# R123A.net
KiCad netlist of a schematic drawn in EAGLE
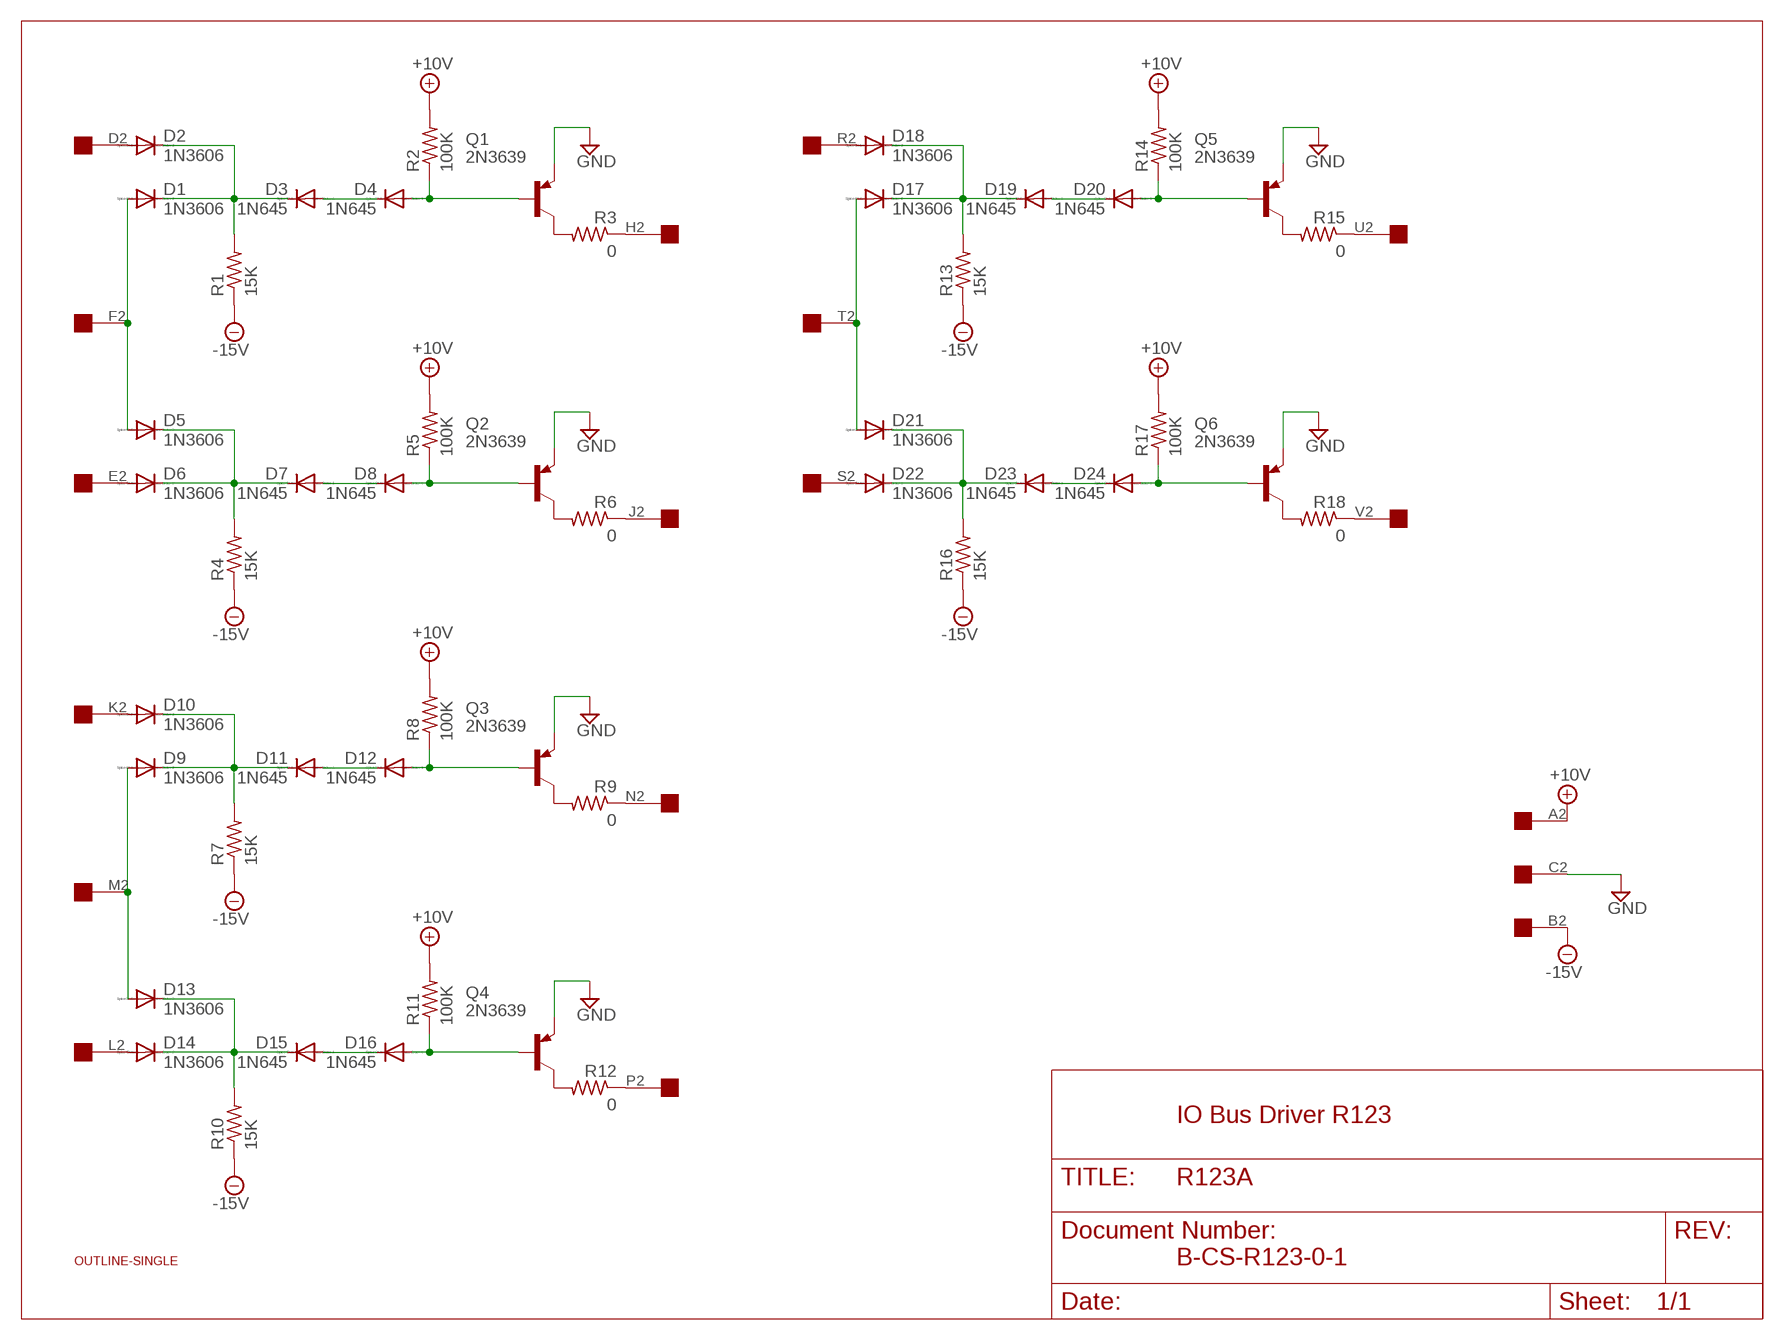
[diagram p0: schematic, sheet 1]

(export (version "E")
  (design (tool "Eeschema 10.0.6"))
  (components
    (comp (ref "D1")
      (value "1N3606")
      (footprint "eagle-import:DO35-10")
      (libsource (lib "eagle-import") (part "1N4148DO35-10"))
    )
    (comp (ref "D2")
      (value "1N3606")
      (footprint "eagle-import:DO35-10")
      (libsource (lib "eagle-import") (part "1N4148DO35-10"))
    )
    (comp (ref "D3")
      (value "1N645")
      (footprint "eagle-import:DO35-10")
      (libsource (lib "eagle-import") (part "1N4148DO35-10"))
    )
    (comp (ref "D4")
      (value "1N645")
      (footprint "eagle-import:DO35-10")
      (libsource (lib "eagle-import") (part "1N4148DO35-10"))
    )
    (comp (ref "D5")
      (value "1N3606")
      (footprint "eagle-import:DO35-10")
      (libsource (lib "eagle-import") (part "1N4148DO35-10"))
    )
    (comp (ref "D6")
      (value "1N3606")
      (footprint "eagle-import:DO35-10")
      (libsource (lib "eagle-import") (part "1N4148DO35-10"))
    )
    (comp (ref "D7")
      (value "1N645")
      (footprint "eagle-import:DO35-10")
      (libsource (lib "eagle-import") (part "1N4148DO35-10"))
    )
    (comp (ref "D8")
      (value "1N645")
      (footprint "eagle-import:DO35-10")
      (libsource (lib "eagle-import") (part "1N4148DO35-10"))
    )
    (comp (ref "D9")
      (value "1N3606")
      (footprint "eagle-import:DO35-10")
      (libsource (lib "eagle-import") (part "1N4148DO35-10"))
    )
    (comp (ref "D10")
      (value "1N3606")
      (footprint "eagle-import:DO35-10")
      (libsource (lib "eagle-import") (part "1N4148DO35-10"))
    )
    (comp (ref "D11")
      (value "1N645")
      (footprint "eagle-import:DO35-10")
      (libsource (lib "eagle-import") (part "1N4148DO35-10"))
    )
    (comp (ref "D12")
      (value "1N645")
      (footprint "eagle-import:DO35-10")
      (libsource (lib "eagle-import") (part "1N4148DO35-10"))
    )
    (comp (ref "D13")
      (value "1N3606")
      (footprint "eagle-import:DO35-10")
      (libsource (lib "eagle-import") (part "1N4148DO35-10"))
    )
    (comp (ref "D14")
      (value "1N3606")
      (footprint "eagle-import:DO35-10")
      (libsource (lib "eagle-import") (part "1N4148DO35-10"))
    )
    (comp (ref "D15")
      (value "1N645")
      (footprint "eagle-import:DO35-10")
      (libsource (lib "eagle-import") (part "1N4148DO35-10"))
    )
    (comp (ref "D16")
      (value "1N645")
      (footprint "eagle-import:DO35-10")
      (libsource (lib "eagle-import") (part "1N4148DO35-10"))
    )
    (comp (ref "D17")
      (value "1N3606")
      (footprint "eagle-import:DO35-10")
      (libsource (lib "eagle-import") (part "1N4148DO35-10"))
    )
    (comp (ref "D18")
      (value "1N3606")
      (footprint "eagle-import:DO35-10")
      (libsource (lib "eagle-import") (part "1N4148DO35-10"))
    )
    (comp (ref "D19")
      (value "1N645")
      (footprint "eagle-import:DO35-10")
      (libsource (lib "eagle-import") (part "1N4148DO35-10"))
    )
    (comp (ref "D20")
      (value "1N645")
      (footprint "eagle-import:DO35-10")
      (libsource (lib "eagle-import") (part "1N4148DO35-10"))
    )
    (comp (ref "D21")
      (value "1N3606")
      (footprint "eagle-import:DO35-10")
      (libsource (lib "eagle-import") (part "1N4148DO35-10"))
    )
    (comp (ref "D22")
      (value "1N3606")
      (footprint "eagle-import:DO35-10")
      (libsource (lib "eagle-import") (part "1N4148DO35-10"))
    )
    (comp (ref "D23")
      (value "1N645")
      (footprint "eagle-import:DO35-10")
      (libsource (lib "eagle-import") (part "1N4148DO35-10"))
    )
    (comp (ref "D24")
      (value "1N645")
      (footprint "eagle-import:DO35-10")
      (libsource (lib "eagle-import") (part "1N4148DO35-10"))
    )
    (comp (ref "Q1")
      (value "2N3639")
      (footprint "eagle-import:TO39")
      (libsource (lib "eagle-import") (part "2N3637"))
    )
    (comp (ref "Q2")
      (value "2N3639")
      (footprint "eagle-import:TO39")
      (libsource (lib "eagle-import") (part "2N3637"))
    )
    (comp (ref "Q3")
      (value "2N3639")
      (footprint "eagle-import:TO39")
      (libsource (lib "eagle-import") (part "2N3637"))
    )
    (comp (ref "Q4")
      (value "2N3639")
      (footprint "eagle-import:TO39")
      (libsource (lib "eagle-import") (part "2N3637"))
    )
    (comp (ref "Q5")
      (value "2N3639")
      (footprint "eagle-import:TO39")
      (libsource (lib "eagle-import") (part "2N3637"))
    )
    (comp (ref "Q6")
      (value "2N3639")
      (footprint "eagle-import:TO39")
      (libsource (lib "eagle-import") (part "2N3637"))
    )
    (comp (ref "R1")
      (value "15K")
      (footprint "eagle-import:0207_10")
      (libsource (lib "eagle-import") (part "R-US_0207/10"))
    )
    (comp (ref "R2")
      (value "100K")
      (footprint "eagle-import:0207_10")
      (libsource (lib "eagle-import") (part "R-US_0207/10"))
    )
    (comp (ref "R3")
      (value "0")
      (footprint "eagle-import:0207_10")
      (libsource (lib "eagle-import") (part "R-US_0207/10"))
    )
    (comp (ref "R4")
      (value "15K")
      (footprint "eagle-import:0207_10")
      (libsource (lib "eagle-import") (part "R-US_0207/10"))
    )
    (comp (ref "R5")
      (value "100K")
      (footprint "eagle-import:0207_10")
      (libsource (lib "eagle-import") (part "R-US_0207/10"))
    )
    (comp (ref "R6")
      (value "0")
      (footprint "eagle-import:0207_10")
      (libsource (lib "eagle-import") (part "R-US_0207/10"))
    )
    (comp (ref "R7")
      (value "15K")
      (footprint "eagle-import:0207_10")
      (libsource (lib "eagle-import") (part "R-US_0207/10"))
    )
    (comp (ref "R8")
      (value "100K")
      (footprint "eagle-import:0207_10")
      (libsource (lib "eagle-import") (part "R-US_0207/10"))
    )
    (comp (ref "R9")
      (value "0")
      (footprint "eagle-import:0207_10")
      (libsource (lib "eagle-import") (part "R-US_0207/10"))
    )
    (comp (ref "R10")
      (value "15K")
      (footprint "eagle-import:0207_10")
      (libsource (lib "eagle-import") (part "R-US_0207/10"))
    )
    (comp (ref "R11")
      (value "100K")
      (footprint "eagle-import:0207_10")
      (libsource (lib "eagle-import") (part "R-US_0207/10"))
    )
    (comp (ref "R12")
      (value "0")
      (footprint "eagle-import:0207_10")
      (libsource (lib "eagle-import") (part "R-US_0207/10"))
    )
    (comp (ref "R13")
      (value "15K")
      (footprint "eagle-import:0207_10")
      (libsource (lib "eagle-import") (part "R-US_0207/10"))
    )
    (comp (ref "R14")
      (value "100K")
      (footprint "eagle-import:0207_10")
      (libsource (lib "eagle-import") (part "R-US_0207/10"))
    )
    (comp (ref "R15")
      (value "0")
      (footprint "eagle-import:0207_10")
      (libsource (lib "eagle-import") (part "R-US_0207/10"))
    )
    (comp (ref "R16")
      (value "15K")
      (footprint "eagle-import:0207_10")
      (libsource (lib "eagle-import") (part "R-US_0207/10"))
    )
    (comp (ref "R17")
      (value "100K")
      (footprint "eagle-import:0207_10")
      (libsource (lib "eagle-import") (part "R-US_0207/10"))
    )
    (comp (ref "R18")
      (value "0")
      (footprint "eagle-import:0207_10")
      (libsource (lib "eagle-import") (part "R-US_0207/10"))
    )
    (comp (ref "U$1")
      (value "OUTLINE-SINGLE")
      (footprint "eagle-import:SINGLE")
      (libsource (lib "eagle-import") (part "OUTLINE-SINGLE"))
    )
    (comp (ref "U$2")
      (value "EDGE-1")
      (footprint "eagle-import:EDGE-CON1")
      (libsource (lib "eagle-import") (part "EDGE-1"))
    )
  )
  (nets
    (net (code "1") (name "+10V") (class "Default")
      (node (ref "R11") (pin "2") (pinfunction "2_2") (pintype "passive"))
      (node (ref "R14") (pin "2") (pinfunction "2_2") (pintype "passive"))
      (node (ref "R17") (pin "2") (pinfunction "2_2") (pintype "passive"))
      (node (ref "R2") (pin "2") (pinfunction "2_2") (pintype "passive"))
      (node (ref "R5") (pin "2") (pinfunction "2_2") (pintype "passive"))
      (node (ref "R8") (pin "2") (pinfunction "2_2") (pintype "passive"))
      (node (ref "U$2") (pin "A2") (pinfunction "1_A2") (pintype "bidirectional"))
    )
    (net (code "2") (name "-15V") (class "Default")
      (node (ref "R1") (pin "1") (pinfunction "1_1") (pintype "passive"))
      (node (ref "R10") (pin "1") (pinfunction "1_1") (pintype "passive"))
      (node (ref "R13") (pin "1") (pinfunction "1_1") (pintype "passive"))
      (node (ref "R16") (pin "1") (pinfunction "1_1") (pintype "passive"))
      (node (ref "R4") (pin "1") (pinfunction "1_1") (pintype "passive"))
      (node (ref "R7") (pin "1") (pinfunction "1_1") (pintype "passive"))
      (node (ref "U$2") (pin "B2") (pinfunction "1_B2") (pintype "bidirectional"))
    )
    (net (code "3") (name "GND") (class "Default")
      (node (ref "Q1") (pin "1") (pinfunction "E_1") (pintype "passive"))
      (node (ref "Q2") (pin "1") (pinfunction "E_1") (pintype "passive"))
      (node (ref "Q3") (pin "1") (pinfunction "E_1") (pintype "passive"))
      (node (ref "Q4") (pin "1") (pinfunction "E_1") (pintype "passive"))
      (node (ref "Q5") (pin "1") (pinfunction "E_1") (pintype "passive"))
      (node (ref "Q6") (pin "1") (pinfunction "E_1") (pintype "passive"))
      (node (ref "U$2") (pin "C2") (pinfunction "1_C2") (pintype "bidirectional"))
    )
    (net (code "4") (name "Net-(D1-PadC)") (class "Default")
      (node (ref "D1") (pin "C") (pinfunction "C_C") (pintype "passive"))
      (node (ref "D2") (pin "C") (pinfunction "C_C") (pintype "passive"))
      (node (ref "D3") (pin "C") (pinfunction "C_C") (pintype "passive"))
      (node (ref "R1") (pin "2") (pinfunction "2_2") (pintype "passive"))
    )
    (net (code "5") (name "Net-(D3-PadA)") (class "Default")
      (node (ref "D3") (pin "A") (pinfunction "A_A") (pintype "passive"))
      (node (ref "D4") (pin "C") (pinfunction "C_C") (pintype "passive"))
    )
    (net (code "6") (name "Net-(D5-PadC)") (class "Default")
      (node (ref "D5") (pin "C") (pinfunction "C_C") (pintype "passive"))
      (node (ref "D6") (pin "C") (pinfunction "C_C") (pintype "passive"))
      (node (ref "D7") (pin "C") (pinfunction "C_C") (pintype "passive"))
      (node (ref "R4") (pin "2") (pinfunction "2_2") (pintype "passive"))
    )
    (net (code "7") (name "Net-(D7-PadA)") (class "Default")
      (node (ref "D7") (pin "A") (pinfunction "A_A") (pintype "passive"))
      (node (ref "D8") (pin "C") (pinfunction "C_C") (pintype "passive"))
    )
    (net (code "8") (name "Net-(D10-PadC)") (class "Default")
      (node (ref "D10") (pin "C") (pinfunction "C_C") (pintype "passive"))
      (node (ref "D11") (pin "C") (pinfunction "C_C") (pintype "passive"))
      (node (ref "D9") (pin "C") (pinfunction "C_C") (pintype "passive"))
      (node (ref "R7") (pin "2") (pinfunction "2_2") (pintype "passive"))
    )
    (net (code "9") (name "Net-(D11-PadA)") (class "Default")
      (node (ref "D11") (pin "A") (pinfunction "A_A") (pintype "passive"))
      (node (ref "D12") (pin "C") (pinfunction "C_C") (pintype "passive"))
    )
    (net (code "10") (name "Net-(D13-PadC)") (class "Default")
      (node (ref "D13") (pin "C") (pinfunction "C_C") (pintype "passive"))
      (node (ref "D14") (pin "C") (pinfunction "C_C") (pintype "passive"))
      (node (ref "D15") (pin "C") (pinfunction "C_C") (pintype "passive"))
      (node (ref "R10") (pin "2") (pinfunction "2_2") (pintype "passive"))
    )
    (net (code "11") (name "Net-(D15-PadA)") (class "Default")
      (node (ref "D15") (pin "A") (pinfunction "A_A") (pintype "passive"))
      (node (ref "D16") (pin "C") (pinfunction "C_C") (pintype "passive"))
    )
    (net (code "12") (name "Net-(D17-PadC)") (class "Default")
      (node (ref "D17") (pin "C") (pinfunction "C_C") (pintype "passive"))
      (node (ref "D18") (pin "C") (pinfunction "C_C") (pintype "passive"))
      (node (ref "D19") (pin "C") (pinfunction "C_C") (pintype "passive"))
      (node (ref "R13") (pin "2") (pinfunction "2_2") (pintype "passive"))
    )
    (net (code "13") (name "Net-(D19-PadA)") (class "Default")
      (node (ref "D19") (pin "A") (pinfunction "A_A") (pintype "passive"))
      (node (ref "D20") (pin "C") (pinfunction "C_C") (pintype "passive"))
    )
    (net (code "14") (name "Net-(D21-PadC)") (class "Default")
      (node (ref "D21") (pin "C") (pinfunction "C_C") (pintype "passive"))
      (node (ref "D22") (pin "C") (pinfunction "C_C") (pintype "passive"))
      (node (ref "D23") (pin "C") (pinfunction "C_C") (pintype "passive"))
      (node (ref "R16") (pin "2") (pinfunction "2_2") (pintype "passive"))
    )
    (net (code "15") (name "Net-(D23-PadA)") (class "Default")
      (node (ref "D23") (pin "A") (pinfunction "A_A") (pintype "passive"))
      (node (ref "D24") (pin "C") (pinfunction "C_C") (pintype "passive"))
    )
    (net (code "16") (name "Net-(Q1-B)") (class "Default")
      (node (ref "D4") (pin "A") (pinfunction "A_A") (pintype "passive"))
      (node (ref "Q1") (pin "2") (pinfunction "B_2") (pintype "passive"))
      (node (ref "R2") (pin "1") (pinfunction "1_1") (pintype "passive"))
    )
    (net (code "17") (name "Net-(Q1-C)") (class "Default")
      (node (ref "Q1") (pin "3") (pinfunction "C_3") (pintype "passive"))
      (node (ref "R3") (pin "2") (pinfunction "2_2") (pintype "passive"))
    )
    (net (code "18") (name "Net-(Q2-B)") (class "Default")
      (node (ref "D8") (pin "A") (pinfunction "A_A") (pintype "passive"))
      (node (ref "Q2") (pin "2") (pinfunction "B_2") (pintype "passive"))
      (node (ref "R5") (pin "1") (pinfunction "1_1") (pintype "passive"))
    )
    (net (code "19") (name "Net-(Q2-C)") (class "Default")
      (node (ref "Q2") (pin "3") (pinfunction "C_3") (pintype "passive"))
      (node (ref "R6") (pin "2") (pinfunction "2_2") (pintype "passive"))
    )
    (net (code "20") (name "Net-(Q3-B)") (class "Default")
      (node (ref "D12") (pin "A") (pinfunction "A_A") (pintype "passive"))
      (node (ref "Q3") (pin "2") (pinfunction "B_2") (pintype "passive"))
      (node (ref "R8") (pin "1") (pinfunction "1_1") (pintype "passive"))
    )
    (net (code "21") (name "Net-(Q3-C)") (class "Default")
      (node (ref "Q3") (pin "3") (pinfunction "C_3") (pintype "passive"))
      (node (ref "R9") (pin "2") (pinfunction "2_2") (pintype "passive"))
    )
    (net (code "22") (name "Net-(Q4-B)") (class "Default")
      (node (ref "D16") (pin "A") (pinfunction "A_A") (pintype "passive"))
      (node (ref "Q4") (pin "2") (pinfunction "B_2") (pintype "passive"))
      (node (ref "R11") (pin "1") (pinfunction "1_1") (pintype "passive"))
    )
    (net (code "23") (name "Net-(Q4-C)") (class "Default")
      (node (ref "Q4") (pin "3") (pinfunction "C_3") (pintype "passive"))
      (node (ref "R12") (pin "2") (pinfunction "2_2") (pintype "passive"))
    )
    (net (code "24") (name "Net-(Q5-B)") (class "Default")
      (node (ref "D20") (pin "A") (pinfunction "A_A") (pintype "passive"))
      (node (ref "Q5") (pin "2") (pinfunction "B_2") (pintype "passive"))
      (node (ref "R14") (pin "1") (pinfunction "1_1") (pintype "passive"))
    )
    (net (code "25") (name "Net-(Q5-C)") (class "Default")
      (node (ref "Q5") (pin "3") (pinfunction "C_3") (pintype "passive"))
      (node (ref "R15") (pin "2") (pinfunction "2_2") (pintype "passive"))
    )
    (net (code "26") (name "Net-(Q6-B)") (class "Default")
      (node (ref "D24") (pin "A") (pinfunction "A_A") (pintype "passive"))
      (node (ref "Q6") (pin "2") (pinfunction "B_2") (pintype "passive"))
      (node (ref "R17") (pin "1") (pinfunction "1_1") (pintype "passive"))
    )
    (net (code "27") (name "Net-(Q6-C)") (class "Default")
      (node (ref "Q6") (pin "3") (pinfunction "C_3") (pintype "passive"))
      (node (ref "R18") (pin "2") (pinfunction "2_2") (pintype "passive"))
    )
    (net (code "28") (name "Net-(U$2D-1)") (class "Default")
      (node (ref "D2") (pin "A") (pinfunction "A_A") (pintype "passive"))
      (node (ref "U$2") (pin "D2") (pinfunction "1_D2") (pintype "bidirectional"))
    )
    (net (code "29") (name "Net-(U$2E-1)") (class "Default")
      (node (ref "D6") (pin "A") (pinfunction "A_A") (pintype "passive"))
      (node (ref "U$2") (pin "E2") (pinfunction "1_E2") (pintype "bidirectional"))
    )
    (net (code "30") (name "Net-(U$2F-1)") (class "Default")
      (node (ref "D1") (pin "A") (pinfunction "A_A") (pintype "passive"))
      (node (ref "D5") (pin "A") (pinfunction "A_A") (pintype "passive"))
      (node (ref "U$2") (pin "F2") (pinfunction "1_F2") (pintype "bidirectional"))
    )
    (net (code "31") (name "Net-(U$2G-1)") (class "Default")
      (node (ref "R3") (pin "1") (pinfunction "1_1") (pintype "passive"))
      (node (ref "U$2") (pin "H2") (pinfunction "1_H2") (pintype "bidirectional"))
    )
    (net (code "32") (name "Net-(U$2H-1)") (class "Default")
      (node (ref "R6") (pin "1") (pinfunction "1_1") (pintype "passive"))
      (node (ref "U$2") (pin "J2") (pinfunction "1_J2") (pintype "bidirectional"))
    )
    (net (code "33") (name "Net-(U$2I-1)") (class "Default")
      (node (ref "D10") (pin "A") (pinfunction "A_A") (pintype "passive"))
      (node (ref "U$2") (pin "K2") (pinfunction "1_K2") (pintype "bidirectional"))
    )
    (net (code "34") (name "Net-(U$2J-1)") (class "Default")
      (node (ref "D14") (pin "A") (pinfunction "A_A") (pintype "passive"))
      (node (ref "U$2") (pin "L2") (pinfunction "1_L2") (pintype "bidirectional"))
    )
    (net (code "35") (name "Net-(U$2K-1)") (class "Default")
      (node (ref "D13") (pin "A") (pinfunction "A_A") (pintype "passive"))
      (node (ref "D9") (pin "A") (pinfunction "A_A") (pintype "passive"))
      (node (ref "U$2") (pin "M2") (pinfunction "1_M2") (pintype "bidirectional"))
    )
    (net (code "36") (name "Net-(U$2L-1)") (class "Default")
      (node (ref "R9") (pin "1") (pinfunction "1_1") (pintype "passive"))
      (node (ref "U$2") (pin "N2") (pinfunction "1_N2") (pintype "bidirectional"))
    )
    (net (code "37") (name "Net-(U$2M-1)") (class "Default")
      (node (ref "R12") (pin "1") (pinfunction "1_1") (pintype "passive"))
      (node (ref "U$2") (pin "P2") (pinfunction "1_P2") (pintype "bidirectional"))
    )
    (net (code "38") (name "Net-(U$2N-1)") (class "Default")
      (node (ref "D18") (pin "A") (pinfunction "A_A") (pintype "passive"))
      (node (ref "U$2") (pin "R2") (pinfunction "1_R2") (pintype "bidirectional"))
    )
    (net (code "39") (name "Net-(U$2O-1)") (class "Default")
      (node (ref "D22") (pin "A") (pinfunction "A_A") (pintype "passive"))
      (node (ref "U$2") (pin "S2") (pinfunction "1_S2") (pintype "bidirectional"))
    )
    (net (code "40") (name "Net-(U$2P-1)") (class "Default")
      (node (ref "D17") (pin "A") (pinfunction "A_A") (pintype "passive"))
      (node (ref "D21") (pin "A") (pinfunction "A_A") (pintype "passive"))
      (node (ref "U$2") (pin "T2") (pinfunction "1_T2") (pintype "bidirectional"))
    )
    (net (code "41") (name "Net-(U$2Q-1)") (class "Default")
      (node (ref "R15") (pin "1") (pinfunction "1_1") (pintype "passive"))
      (node (ref "U$2") (pin "U2") (pinfunction "1_U2") (pintype "bidirectional"))
    )
    (net (code "42") (name "Net-(U$2R-1)") (class "Default")
      (node (ref "R18") (pin "1") (pinfunction "1_1") (pintype "passive"))
      (node (ref "U$2") (pin "V2") (pinfunction "1_V2") (pintype "bidirectional"))
    )
  )
)
